# hd-hdr.net
KiCad netlist of a schematic drawn in Altium Designer
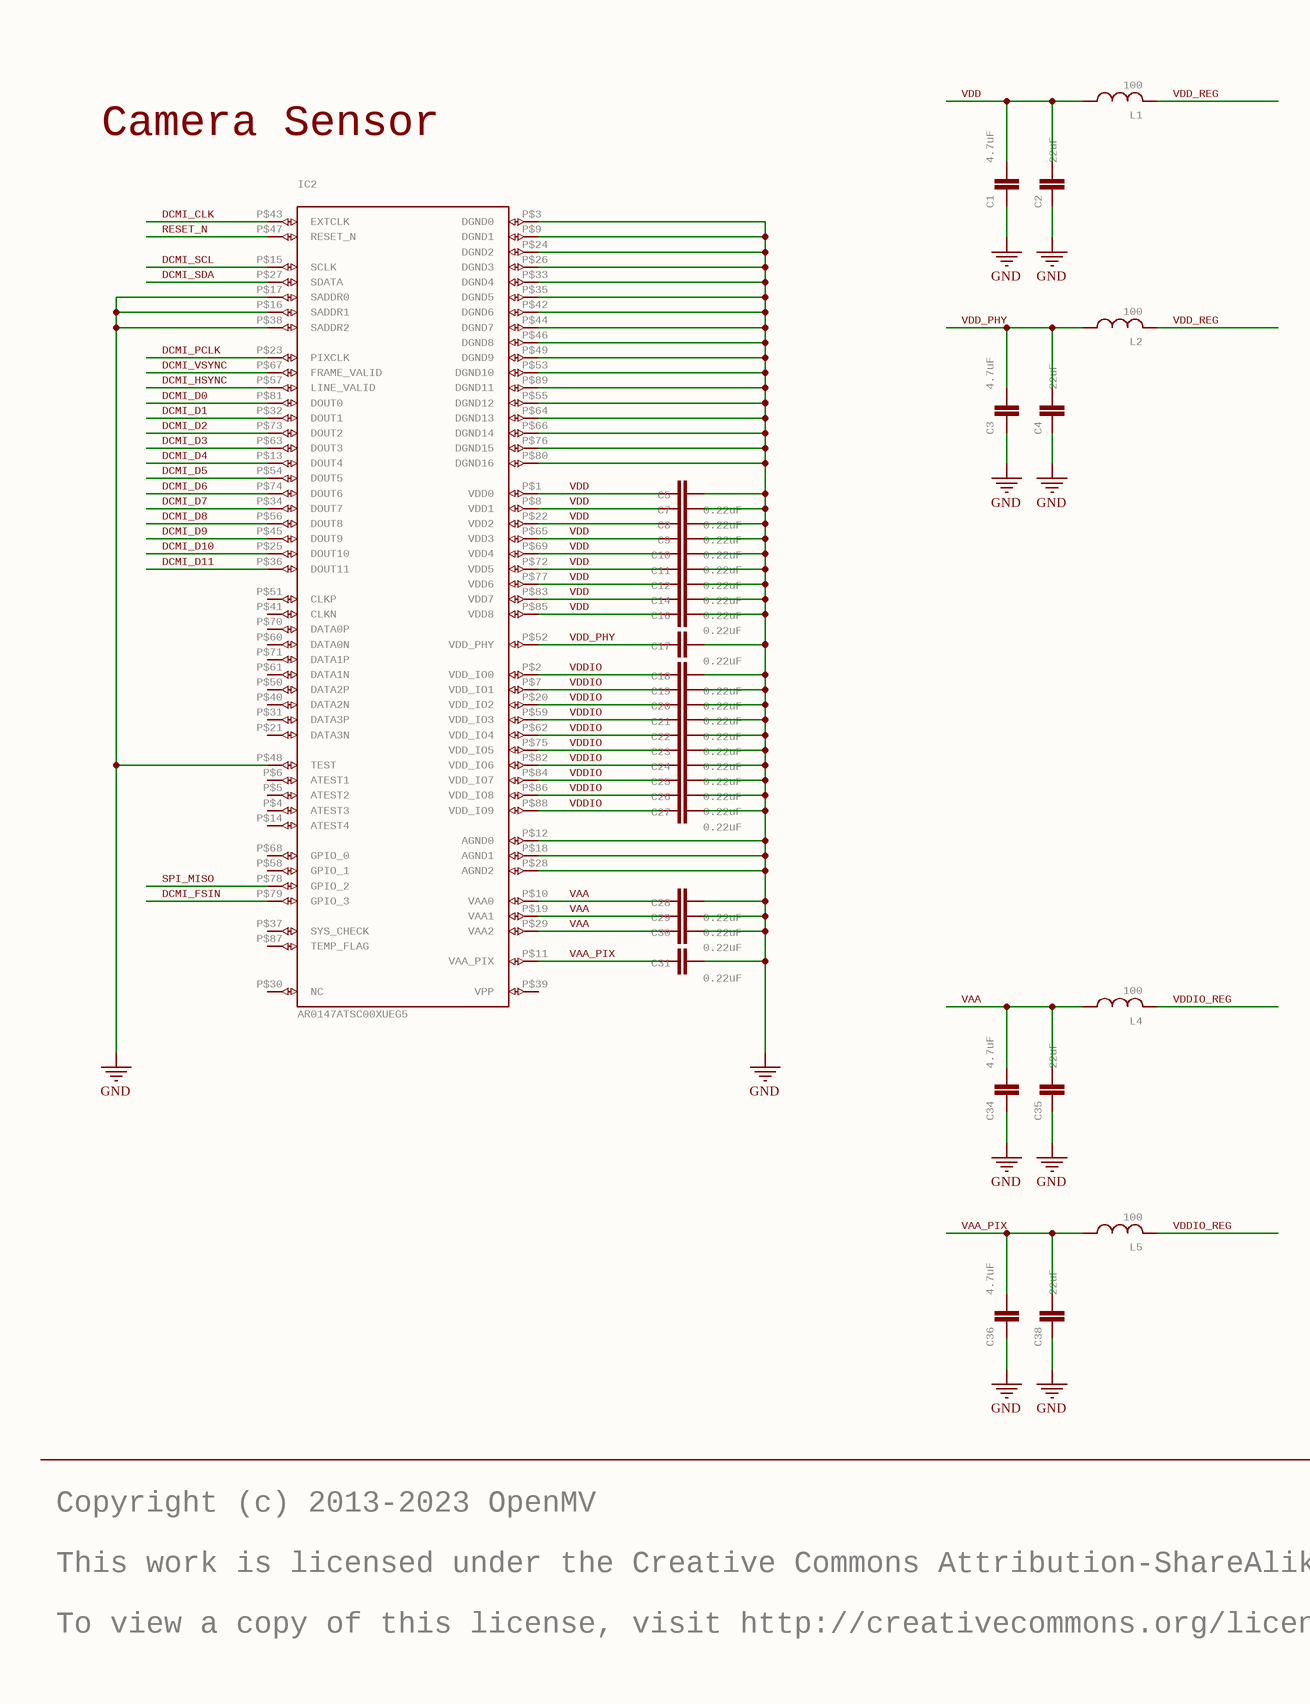
[diagram p0: hd-hdr.SchDoc, left]
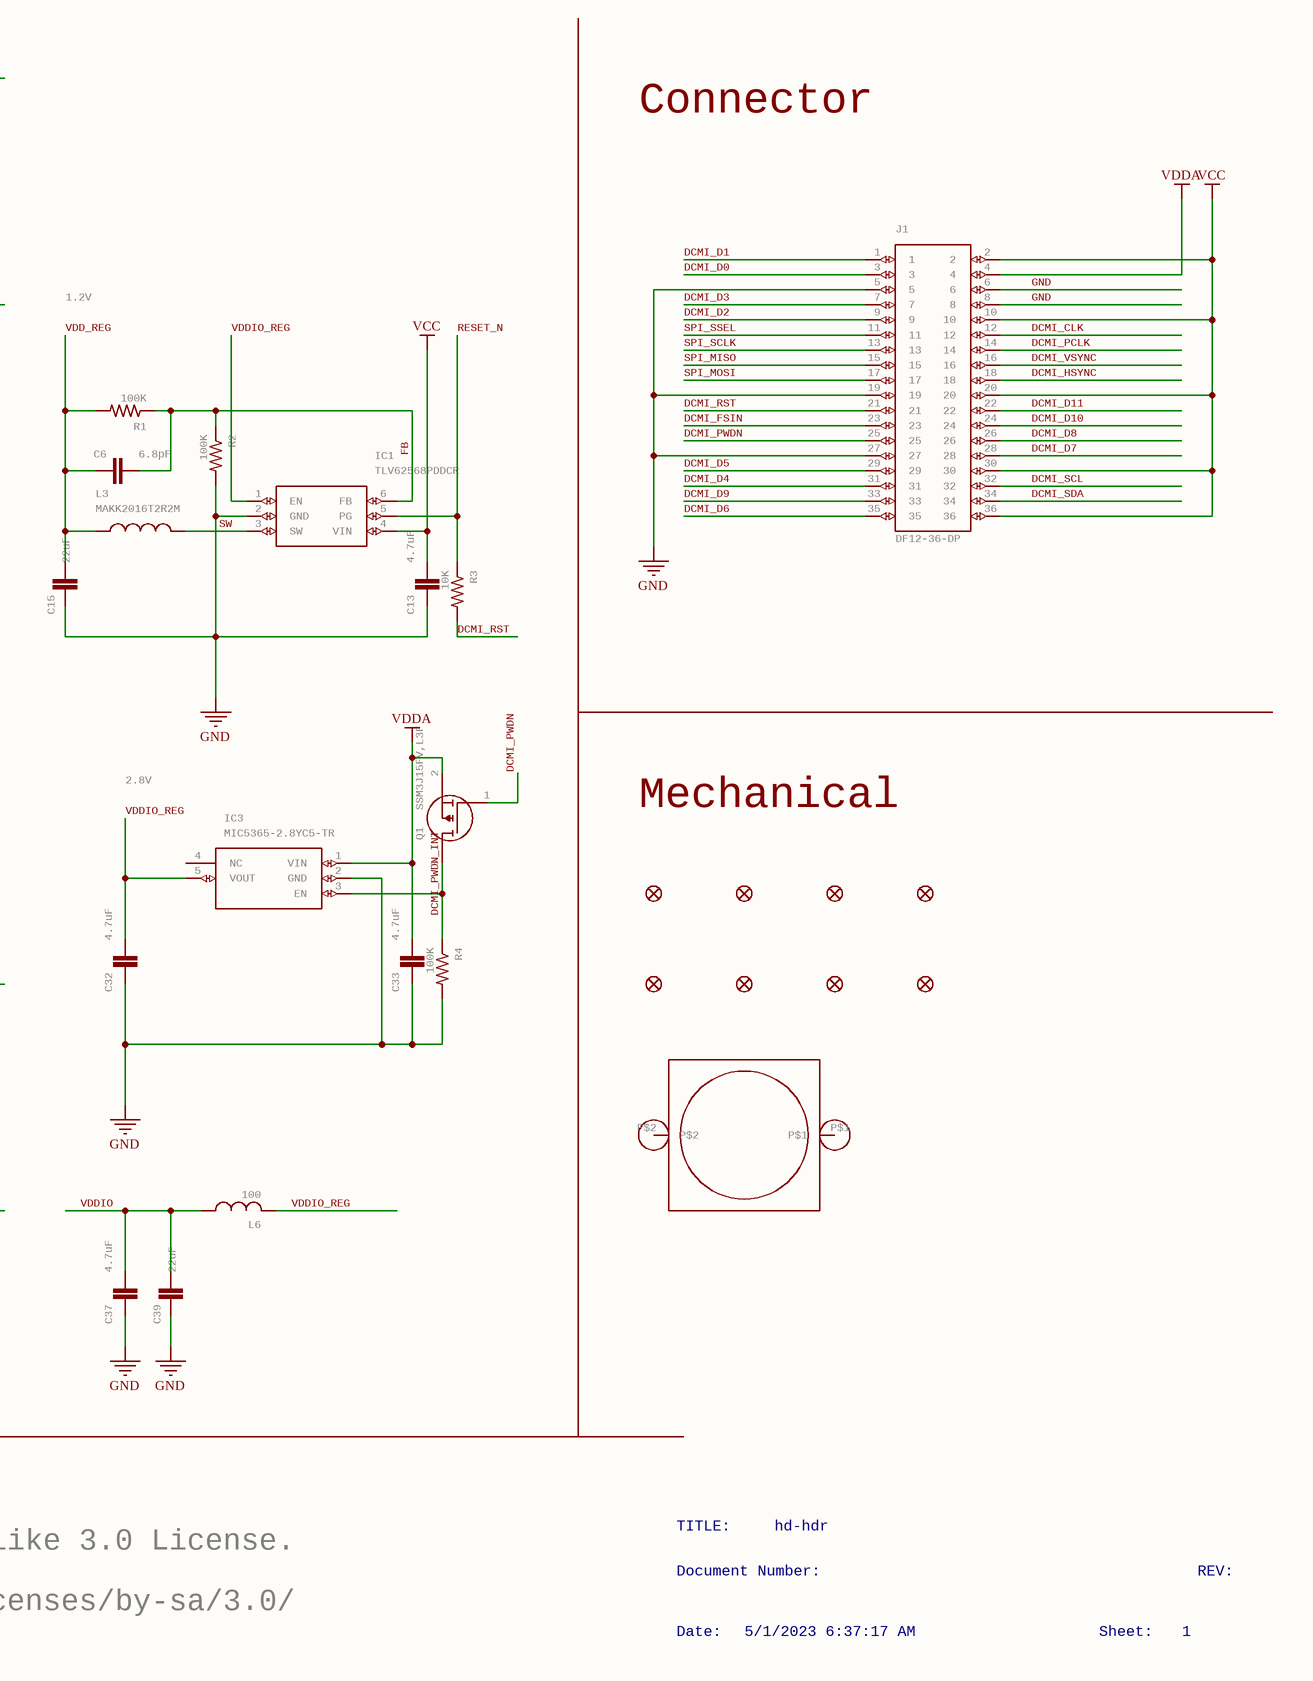
[diagram p1: hd-hdr.SchDoc, right]

(export (version "E")
  (design (tool "Eeschema 10.0.6"))
  (components
    (comp (ref "C1")
      (value "4.7uF")
      (footprint "0402")
      (description "0402 (1005 Metric) Nick Garner - TeleSense")
      (fields (field (name "MPN") "JMK105BBJ475MV-F"))
      (libsource (lib "camera-modules") (part "CAP_0402"))
    )
    (comp (ref "C2")
      (value "22uF")
      (footprint "0805")
      (fields (field (name "MPN") "CL21A226MQQNNNE"))
      (libsource (lib "camera-modules") (part "22UF-0805-6.3V-20%"))
    )
    (comp (ref "C3")
      (value "4.7uF")
      (footprint "0402")
      (description "0402 (1005 Metric) Nick Garner - TeleSense")
      (fields (field (name "MPN") "JMK105BBJ475MV-F"))
      (libsource (lib "camera-modules") (part "CAP_0402"))
    )
    (comp (ref "C4")
      (value "22uF")
      (footprint "0805")
      (fields (field (name "MPN") "CL21A226MQQNNNE"))
      (libsource (lib "camera-modules") (part "22UF-0805-6.3V-20%"))
    )
    (comp (ref "C5")
      (value "0.22uF")
      (footprint "C0201")
      (description "CAPACITOR, European symbol")
      (fields (field (name "MPN") "GRM033R60J224ME15D"))
      (libsource (lib "camera-modules") (part "C-EUC0201"))
    )
    (comp (ref "C6")
      (value "6.8pF")
      (footprint "0402")
      (description "0402 (1005 Metric) Nick Garner - TeleSense")
      (fields (field (name "MPN") "GRM1555C1H6R8DA01D"))
      (libsource (lib "") (part "CAP_0402_1"))
    )
    (comp (ref "C7")
      (value "0.22uF")
      (footprint "C0201")
      (description "CAPACITOR, European symbol")
      (fields (field (name "MPN") "GRM033R60J224ME15D"))
      (libsource (lib "camera-modules") (part "C-EUC0201"))
    )
    (comp (ref "C8")
      (value "0.22uF")
      (footprint "C0201")
      (description "CAPACITOR, European symbol")
      (fields (field (name "MPN") "GRM033R60J224ME15D"))
      (libsource (lib "camera-modules") (part "C-EUC0201"))
    )
    (comp (ref "C9")
      (value "0.22uF")
      (footprint "C0201")
      (description "CAPACITOR, European symbol")
      (fields (field (name "MPN") "GRM033R60J224ME15D"))
      (libsource (lib "camera-modules") (part "C-EUC0201"))
    )
    (comp (ref "C10")
      (value "0.22uF")
      (footprint "C0201")
      (description "CAPACITOR, European symbol")
      (fields (field (name "MPN") "GRM033R60J224ME15D"))
      (libsource (lib "camera-modules") (part "C-EUC0201"))
    )
    (comp (ref "C11")
      (value "0.22uF")
      (footprint "C0201")
      (description "CAPACITOR, European symbol")
      (fields (field (name "MPN") "GRM033R60J224ME15D"))
      (libsource (lib "camera-modules") (part "C-EUC0201"))
    )
    (comp (ref "C12")
      (value "0.22uF")
      (footprint "C0201")
      (description "CAPACITOR, European symbol")
      (fields (field (name "MPN") "GRM033R60J224ME15D"))
      (libsource (lib "camera-modules") (part "C-EUC0201"))
    )
    (comp (ref "C13")
      (value "4.7uF")
      (footprint "0402")
      (description "0402 (1005 Metric) Nick Garner - TeleSense")
      (fields (field (name "MPN") "JMK105BBJ475MV-F"))
      (libsource (lib "camera-modules") (part "CAP_0402"))
    )
    (comp (ref "C14")
      (value "0.22uF")
      (footprint "C0201")
      (description "CAPACITOR, European symbol")
      (fields (field (name "MPN") "GRM033R60J224ME15D"))
      (libsource (lib "camera-modules") (part "C-EUC0201"))
    )
    (comp (ref "C15")
      (value "22uF")
      (footprint "0805")
      (fields (field (name "MPN") "CL21A226MQQNNNE"))
      (libsource (lib "camera-modules") (part "22UF-0805-6.3V-20%"))
    )
    (comp (ref "C16")
      (value "0.22uF")
      (footprint "C0201")
      (description "CAPACITOR, European symbol")
      (fields (field (name "MPN") "GRM033R60J224ME15D"))
      (libsource (lib "camera-modules") (part "C-EUC0201"))
    )
    (comp (ref "C17")
      (value "0.22uF")
      (footprint "C0201")
      (description "CAPACITOR, European symbol")
      (fields (field (name "MPN") "GRM033R60J224ME15D"))
      (libsource (lib "camera-modules") (part "C-EUC0201"))
    )
    (comp (ref "C18")
      (value "0.22uF")
      (footprint "C0201")
      (description "CAPACITOR, European symbol")
      (fields (field (name "MPN") "GRM033R60J224ME15D"))
      (libsource (lib "camera-modules") (part "C-EUC0201"))
    )
    (comp (ref "C19")
      (value "0.22uF")
      (footprint "C0201")
      (description "CAPACITOR, European symbol")
      (fields (field (name "MPN") "GRM033R60J224ME15D"))
      (libsource (lib "camera-modules") (part "C-EUC0201"))
    )
    (comp (ref "C20")
      (value "0.22uF")
      (footprint "C0201")
      (description "CAPACITOR, European symbol")
      (fields (field (name "MPN") "GRM033R60J224ME15D"))
      (libsource (lib "camera-modules") (part "C-EUC0201"))
    )
    (comp (ref "C21")
      (value "0.22uF")
      (footprint "C0201")
      (description "CAPACITOR, European symbol")
      (fields (field (name "MPN") "GRM033R60J224ME15D"))
      (libsource (lib "camera-modules") (part "C-EUC0201"))
    )
    (comp (ref "C22")
      (value "0.22uF")
      (footprint "C0201")
      (description "CAPACITOR, European symbol")
      (fields (field (name "MPN") "GRM033R60J224ME15D"))
      (libsource (lib "camera-modules") (part "C-EUC0201"))
    )
    (comp (ref "C23")
      (value "0.22uF")
      (footprint "C0201")
      (description "CAPACITOR, European symbol")
      (fields (field (name "MPN") "GRM033R60J224ME15D"))
      (libsource (lib "camera-modules") (part "C-EUC0201"))
    )
    (comp (ref "C24")
      (value "0.22uF")
      (footprint "C0201")
      (description "CAPACITOR, European symbol")
      (fields (field (name "MPN") "GRM033R60J224ME15D"))
      (libsource (lib "camera-modules") (part "C-EUC0201"))
    )
    (comp (ref "C25")
      (value "0.22uF")
      (footprint "C0201")
      (description "CAPACITOR, European symbol")
      (fields (field (name "MPN") "GRM033R60J224ME15D"))
      (libsource (lib "camera-modules") (part "C-EUC0201"))
    )
    (comp (ref "C26")
      (value "0.22uF")
      (footprint "C0201")
      (description "CAPACITOR, European symbol")
      (fields (field (name "MPN") "GRM033R60J224ME15D"))
      (libsource (lib "camera-modules") (part "C-EUC0201"))
    )
    (comp (ref "C27")
      (value "0.22uF")
      (footprint "C0201")
      (description "CAPACITOR, European symbol")
      (fields (field (name "MPN") "GRM033R60J224ME15D"))
      (libsource (lib "camera-modules") (part "C-EUC0201"))
    )
    (comp (ref "C28")
      (value "0.22uF")
      (footprint "C0201")
      (description "CAPACITOR, European symbol")
      (fields (field (name "MPN") "GRM033R60J224ME15D"))
      (libsource (lib "camera-modules") (part "C-EUC0201"))
    )
    (comp (ref "C29")
      (value "0.22uF")
      (footprint "C0201")
      (description "CAPACITOR, European symbol")
      (fields (field (name "MPN") "GRM033R60J224ME15D"))
      (libsource (lib "camera-modules") (part "C-EUC0201"))
    )
    (comp (ref "C30")
      (value "0.22uF")
      (footprint "C0201")
      (description "CAPACITOR, European symbol")
      (fields (field (name "MPN") "GRM033R60J224ME15D"))
      (libsource (lib "camera-modules") (part "C-EUC0201"))
    )
    (comp (ref "C31")
      (value "0.22uF")
      (footprint "C0201")
      (description "CAPACITOR, European symbol")
      (fields (field (name "MPN") "GRM033R60J224ME15D"))
      (libsource (lib "camera-modules") (part "C-EUC0201"))
    )
    (comp (ref "C32")
      (value "4.7uF")
      (footprint "0402")
      (description "0402 (1005 Metric) Nick Garner - TeleSense")
      (fields (field (name "MPN") "JMK105BBJ475MV-F"))
      (libsource (lib "camera-modules") (part "CAP_0402"))
    )
    (comp (ref "C33")
      (value "4.7uF")
      (footprint "0402")
      (description "0402 (1005 Metric) Nick Garner - TeleSense")
      (fields (field (name "MPN") "JMK105BBJ475MV-F"))
      (libsource (lib "camera-modules") (part "CAP_0402"))
    )
    (comp (ref "C34")
      (value "4.7uF")
      (footprint "0402")
      (description "0402 (1005 Metric) Nick Garner - TeleSense")
      (fields (field (name "MPN") "JMK105BBJ475MV-F"))
      (libsource (lib "camera-modules") (part "CAP_0402"))
    )
    (comp (ref "C35")
      (value "22uF")
      (footprint "0805")
      (fields (field (name "MPN") "CL21A226MQQNNNE"))
      (libsource (lib "camera-modules") (part "22UF-0805-6.3V-20%"))
    )
    (comp (ref "C36")
      (value "4.7uF")
      (footprint "0402")
      (description "0402 (1005 Metric) Nick Garner - TeleSense")
      (fields (field (name "MPN") "JMK105BBJ475MV-F"))
      (libsource (lib "camera-modules") (part "CAP_0402"))
    )
    (comp (ref "C37")
      (value "4.7uF")
      (footprint "0402")
      (description "0402 (1005 Metric) Nick Garner - TeleSense")
      (fields (field (name "MPN") "JMK105BBJ475MV-F"))
      (libsource (lib "camera-modules") (part "CAP_0402"))
    )
    (comp (ref "C38")
      (value "22uF")
      (footprint "0805")
      (fields (field (name "MPN") "CL21A226MQQNNNE"))
      (libsource (lib "camera-modules") (part "22UF-0805-6.3V-20%"))
    )
    (comp (ref "C39")
      (value "22uF")
      (footprint "0805")
      (fields (field (name "MPN") "CL21A226MQQNNNE"))
      (libsource (lib "camera-modules") (part "22UF-0805-6.3V-20%"))
    )
    (comp (ref "FD1")
      (value "FIDUCIAL1X2")
      (footprint "FIDUCIAL-1X2")
      (fields (field (name "LIBRARYNAME") "SparkFun-Aesthetics"))
      (libsource (lib "camera-modules") (part "FIDUCIAL1X2"))
    )
    (comp (ref "FD2")
      (value "FIDUCIAL1X2")
      (footprint "FIDUCIAL-1X2")
      (fields (field (name "LIBRARYNAME") "SparkFun-Aesthetics"))
      (libsource (lib "camera-modules") (part "FIDUCIAL1X2"))
    )
    (comp (ref "FD3")
      (value "FIDUCIAL1X2")
      (footprint "FIDUCIAL-1X2")
      (fields (field (name "LIBRARYNAME") "SparkFun-Aesthetics"))
      (libsource (lib "camera-modules") (part "FIDUCIAL1X2"))
    )
    (comp (ref "FD4")
      (value "FIDUCIAL1X2")
      (footprint "FIDUCIAL-1X2")
      (fields (field (name "LIBRARYNAME") "SparkFun-Aesthetics"))
      (libsource (lib "camera-modules") (part "FIDUCIAL1X2"))
    )
    (comp (ref "FD5")
      (value "FIDUCIAL1X2")
      (footprint "FIDUCIAL-1X2")
      (fields (field (name "LIBRARYNAME") "SparkFun-Aesthetics"))
      (libsource (lib "camera-modules") (part "FIDUCIAL1X2"))
    )
    (comp (ref "FD6")
      (value "FIDUCIAL1X2")
      (footprint "FIDUCIAL-1X2")
      (fields (field (name "LIBRARYNAME") "SparkFun-Aesthetics"))
      (libsource (lib "camera-modules") (part "FIDUCIAL1X2"))
    )
    (comp (ref "FD7")
      (value "FIDUCIAL1X2")
      (footprint "FIDUCIAL-1X2")
      (fields (field (name "LIBRARYNAME") "SparkFun-Aesthetics"))
      (libsource (lib "camera-modules") (part "FIDUCIAL1X2"))
    )
    (comp (ref "FD8")
      (value "FIDUCIAL1X2")
      (footprint "FIDUCIAL-1X2")
      (fields (field (name "LIBRARYNAME") "SparkFun-Aesthetics"))
      (libsource (lib "camera-modules") (part "FIDUCIAL1X2"))
    )
    (comp (ref "H1")
      (value "LENSMOUNT20MM")
      (footprint "LENSMOUNT-20MM")
      (libsource (lib "camera-modules") (part "LENSMOUNT20MM"))
    )
    (comp (ref "IC1")
      (value "TLV62568PDDCR")
      (footprint "SOT95P280X110-6N")
      (fields (field (name "MOUSER_PART_NUMBER") "595-TLV62568PDDCR"))
      (libsource (lib "camera-modules") (part "TLV62568PDDCR"))
    )
    (comp (ref "IC2")
      (value "AR0147ATSC00XUEG5")
      (footprint "AR0147ATSC00XUEG5")
      (fields (field (name "MPN") "AR0147ATSC00XUEG5-DRBR"))
      (libsource (lib "camera-modules") (part "AR0147ATSC00XUEG5"))
    )
    (comp (ref "IC3")
      (value "MIC5365-2.8YC5-TR")
      (footprint "SOT65P210X110-5N")
      (description "IC REG LINEAR 2.8V 150MA SC70-5   Source:  Datasheet")
      (fields (field (name "MOUSER_PART_NUMBER") "998-MIC5365-2.8YC5TR"))
      (libsource (lib "camera-modules") (part "MIC5365-2.8YC5-TR"))
    )
    (comp (ref "J1")
      (value "DF12-36-DP")
      (footprint "DF12-36-DP")
      (fields (field (name "MPN") "DF12NB(3.0)-36DP-0.5V(51)"))
      (libsource (lib "camera-modules") (part "DF12-36-DP"))
    )
    (comp (ref "L1")
      (value "100")
      (footprint "0402")
      (fields (field (name "MPN") "MFBM1V1005-101-R"))
      (libsource (lib "camera-modules") (part "INDUCTOR_0402"))
    )
    (comp (ref "L2")
      (value "100")
      (footprint "0402")
      (fields (field (name "MPN") "MFBM1V1005-101-R"))
      (libsource (lib "camera-modules") (part "INDUCTOR_0402"))
    )
    (comp (ref "L3")
      (value "MAKK2016T2R2M")
      (footprint "INDC2016X100N")
      (description "INDUCTOR, METAL CORE Check availability")
      (fields (field (name "MF") "Taiyo Yuden"))
      (libsource (lib "camera-modules") (part "MAKK2016T2R2M"))
    )
    (comp (ref "L4")
      (value "100")
      (footprint "0402")
      (fields (field (name "MPN") "MFBM1V1005-101-R"))
      (libsource (lib "camera-modules") (part "INDUCTOR_0402"))
    )
    (comp (ref "L5")
      (value "100")
      (footprint "0402")
      (fields (field (name "MPN") "MFBM1V1005-101-R"))
      (libsource (lib "camera-modules") (part "INDUCTOR_0402"))
    )
    (comp (ref "L6")
      (value "100")
      (footprint "0402")
      (fields (field (name "MPN") "MFBM1V1005-101-R"))
      (libsource (lib "camera-modules") (part "INDUCTOR_0402"))
    )
    (comp (ref "Q1")
      (value "SSM3J15FV,L3F")
      (footprint "SSM3J15FV")
      (description "MOSFET 30 V, P-channel Trench MOSFET   Source:  Datasheet")
      (libsource (lib "camera-modules") (part "PMXB120EPEZ"))
    )
    (comp (ref "R1")
      (value "100K")
      (footprint "R0402")
      (description "RESISTOR, American symbol")
      (fields (field (name "MPN") "AC0402FR-07100KL"))
      (libsource (lib "camera-modules") (part "R-US_R0402"))
    )
    (comp (ref "R2")
      (value "100K")
      (footprint "R0402")
      (description "RESISTOR, American symbol")
      (fields (field (name "MPN") "AC0402FR-07100KL"))
      (libsource (lib "camera-modules") (part "R-US_R0402"))
    )
    (comp (ref "R3")
      (value "10K")
      (footprint "R0402")
      (description "RESISTOR, American symbol")
      (fields (field (name "MPN") "AC0402FR-1310KL"))
      (libsource (lib "camera-modules") (part "R-US_R0402"))
    )
    (comp (ref "R4")
      (value "100K")
      (footprint "R0402")
      (description "RESISTOR, American symbol")
      (fields (field (name "MPN") "AC0402FR-07100KL"))
      (libsource (lib "camera-modules") (part "R-US_R0402"))
    )
  )
  (nets
    (net (code "1") (name "/DCMI_CLK") (class "Default")
      (node (ref "IC2") (pin "P$43") (pinfunction "EXTCLK_P$43") (pintype "bidirectional"))
      (node (ref "J1") (pin "12") (pinfunction "12_12") (pintype "bidirectional"))
    )
    (net (code "2") (name "/DCMI_D0") (class "Default")
      (node (ref "IC2") (pin "P$81") (pinfunction "DOUT0_P$81") (pintype "bidirectional"))
      (node (ref "J1") (pin "3") (pinfunction "3_3") (pintype "bidirectional"))
    )
    (net (code "3") (name "/DCMI_D1") (class "Default")
      (node (ref "IC2") (pin "P$32") (pinfunction "DOUT1_P$32") (pintype "bidirectional"))
      (node (ref "J1") (pin "1") (pinfunction "1_1") (pintype "bidirectional"))
    )
    (net (code "4") (name "/DCMI_D2") (class "Default")
      (node (ref "IC2") (pin "P$73") (pinfunction "DOUT2_P$73") (pintype "bidirectional"))
      (node (ref "J1") (pin "9") (pinfunction "9_9") (pintype "bidirectional"))
    )
    (net (code "5") (name "/DCMI_D3") (class "Default")
      (node (ref "IC2") (pin "P$63") (pinfunction "DOUT3_P$63") (pintype "bidirectional"))
      (node (ref "J1") (pin "7") (pinfunction "7_7") (pintype "bidirectional"))
    )
    (net (code "6") (name "/DCMI_D4") (class "Default")
      (node (ref "IC2") (pin "P$13") (pinfunction "DOUT4_P$13") (pintype "bidirectional"))
      (node (ref "J1") (pin "31") (pinfunction "31_31") (pintype "bidirectional"))
    )
    (net (code "7") (name "/DCMI_D5") (class "Default")
      (node (ref "IC2") (pin "P$54") (pinfunction "DOUT5_P$54") (pintype "bidirectional"))
      (node (ref "J1") (pin "29") (pinfunction "29_29") (pintype "bidirectional"))
    )
    (net (code "8") (name "/DCMI_D6") (class "Default")
      (node (ref "IC2") (pin "P$74") (pinfunction "DOUT6_P$74") (pintype "bidirectional"))
      (node (ref "J1") (pin "35") (pinfunction "35_35") (pintype "bidirectional"))
    )
    (net (code "9") (name "/DCMI_D7") (class "Default")
      (node (ref "IC2") (pin "P$34") (pinfunction "DOUT7_P$34") (pintype "bidirectional"))
      (node (ref "J1") (pin "28") (pinfunction "28_28") (pintype "bidirectional"))
    )
    (net (code "10") (name "/DCMI_D8") (class "Default")
      (node (ref "IC2") (pin "P$56") (pinfunction "DOUT8_P$56") (pintype "bidirectional"))
      (node (ref "J1") (pin "26") (pinfunction "26_26") (pintype "bidirectional"))
    )
    (net (code "11") (name "/DCMI_D9") (class "Default")
      (node (ref "IC2") (pin "P$45") (pinfunction "DOUT9_P$45") (pintype "bidirectional"))
      (node (ref "J1") (pin "33") (pinfunction "33_33") (pintype "bidirectional"))
    )
    (net (code "12") (name "/DCMI_D10") (class "Default")
      (node (ref "IC2") (pin "P$25") (pinfunction "DOUT10_P$25") (pintype "bidirectional"))
      (node (ref "J1") (pin "24") (pinfunction "24_24") (pintype "bidirectional"))
    )
    (net (code "13") (name "/DCMI_D11") (class "Default")
      (node (ref "IC2") (pin "P$36") (pinfunction "DOUT11_P$36") (pintype "bidirectional"))
      (node (ref "J1") (pin "22") (pinfunction "22_22") (pintype "bidirectional"))
    )
    (net (code "14") (name "/DCMI_FSIN") (class "Default")
      (node (ref "IC2") (pin "P$79") (pinfunction "GPIO_3_P$79") (pintype "bidirectional"))
      (node (ref "J1") (pin "23") (pinfunction "23_23") (pintype "bidirectional"))
    )
    (net (code "15") (name "/DCMI_HSYNC") (class "Default")
      (node (ref "IC2") (pin "P$57") (pinfunction "LINE_VALID_P$57") (pintype "bidirectional"))
      (node (ref "J1") (pin "18") (pinfunction "18_18") (pintype "bidirectional"))
    )
    (net (code "16") (name "/DCMI_PCLK") (class "Default")
      (node (ref "IC2") (pin "P$23") (pinfunction "PIXCLK_P$23") (pintype "bidirectional"))
      (node (ref "J1") (pin "14") (pinfunction "14_14") (pintype "bidirectional"))
    )
    (net (code "17") (name "/DCMI_PWDN") (class "Default")
      (node (ref "J1") (pin "25") (pinfunction "25_25") (pintype "bidirectional"))
      (node (ref "Q1") (pin "1") (pinfunction "G_1") (pintype "bidirectional"))
    )
    (net (code "18") (name "/DCMI_PWDN_INT") (class "Default")
      (node (ref "IC3") (pin "3") (pinfunction "EN_3") (pintype "bidirectional"))
      (node (ref "Q1") (pin "3") (pinfunction "D_3") (pintype "bidirectional"))
      (node (ref "R4") (pin "1") (pinfunction "1_1") (pintype "passive"))
    )
    (net (code "19") (name "/DCMI_RST") (class "Default")
      (node (ref "J1") (pin "21") (pinfunction "21_21") (pintype "bidirectional"))
      (node (ref "R3") (pin "2") (pinfunction "2_2") (pintype "passive"))
    )
    (net (code "20") (name "/DCMI_SCL") (class "Default")
      (node (ref "IC2") (pin "P$15") (pinfunction "SCLK_P$15") (pintype "bidirectional"))
      (node (ref "J1") (pin "32") (pinfunction "32_32") (pintype "bidirectional"))
    )
    (net (code "21") (name "/DCMI_SDA") (class "Default")
      (node (ref "IC2") (pin "P$27") (pinfunction "SDATA_P$27") (pintype "bidirectional"))
      (node (ref "J1") (pin "34") (pinfunction "34_34") (pintype "bidirectional"))
    )
    (net (code "22") (name "/DCMI_VSYNC") (class "Default")
      (node (ref "IC2") (pin "P$67") (pinfunction "FRAME_VALID_P$67") (pintype "bidirectional"))
      (node (ref "J1") (pin "16") (pinfunction "16_16") (pintype "bidirectional"))
    )
    (net (code "23") (name "/FB") (class "Default")
      (node (ref "C6") (pin "2") (pinfunction "2_2") (pintype "passive"))
      (node (ref "IC1") (pin "6") (pinfunction "FB_6") (pintype "bidirectional"))
      (node (ref "R1") (pin "1") (pinfunction "1_1") (pintype "passive"))
      (node (ref "R2") (pin "1") (pinfunction "1_1") (pintype "passive"))
    )
    (net (code "24") (name "/RESET_N") (class "Default")
      (node (ref "IC1") (pin "5") (pinfunction "PG_5") (pintype "bidirectional"))
      (node (ref "IC2") (pin "P$47") (pinfunction "RESET_N_P$47") (pintype "bidirectional"))
      (node (ref "R3") (pin "1") (pinfunction "1_1") (pintype "passive"))
    )
    (net (code "25") (name "/SPI_MISO") (class "Default")
      (node (ref "IC2") (pin "P$78") (pinfunction "GPIO_2_P$78") (pintype "bidirectional"))
      (node (ref "J1") (pin "15") (pinfunction "15_15") (pintype "bidirectional"))
    )
    (net (code "26") (name "/SPI_MOSI") (class "Default")
      (node (ref "J1") (pin "17") (pinfunction "17_17") (pintype "bidirectional"))
    )
    (net (code "27") (name "/SPI_SCLK") (class "Default")
      (node (ref "J1") (pin "13") (pinfunction "13_13") (pintype "bidirectional"))
    )
    (net (code "28") (name "/SPI_SSEL") (class "Default")
      (node (ref "J1") (pin "11") (pinfunction "11_11") (pintype "bidirectional"))
    )
    (net (code "29") (name "/SW") (class "Default")
      (node (ref "IC1") (pin "3") (pinfunction "SW_3") (pintype "bidirectional"))
      (node (ref "L3") (pin "2") (pinfunction "2_2") (pintype "passive"))
    )
    (net (code "30") (name "/VAA") (class "Default")
      (node (ref "C28") (pin "1") (pinfunction "1_1") (pintype "passive"))
      (node (ref "C29") (pin "1") (pinfunction "1_1") (pintype "passive"))
      (node (ref "C30") (pin "1") (pinfunction "1_1") (pintype "passive"))
      (node (ref "C34") (pin "2") (pinfunction "2_2") (pintype "passive"))
      (node (ref "C35") (pin "2") (pinfunction "2_2") (pintype "passive"))
      (node (ref "IC2") (pin "P$10") (pinfunction "VAA0_P$10") (pintype "bidirectional"))
      (node (ref "IC2") (pin "P$19") (pinfunction "VAA1_P$19") (pintype "bidirectional"))
      (node (ref "IC2") (pin "P$29") (pinfunction "VAA2_P$29") (pintype "bidirectional"))
      (node (ref "L4") (pin "1") (pinfunction "P$1_1") (pintype "passive"))
    )
    (net (code "31") (name "/VAA_PIX") (class "Default")
      (node (ref "C31") (pin "1") (pinfunction "1_1") (pintype "passive"))
      (node (ref "C36") (pin "2") (pinfunction "2_2") (pintype "passive"))
      (node (ref "C38") (pin "2") (pinfunction "2_2") (pintype "passive"))
      (node (ref "IC2") (pin "P$11") (pinfunction "VAA_PIX_P$11") (pintype "bidirectional"))
      (node (ref "L5") (pin "1") (pinfunction "P$1_1") (pintype "passive"))
    )
    (net (code "32") (name "/VDD") (class "Default")
      (node (ref "C1") (pin "2") (pinfunction "2_2") (pintype "passive"))
      (node (ref "C10") (pin "1") (pinfunction "1_1") (pintype "passive"))
      (node (ref "C11") (pin "1") (pinfunction "1_1") (pintype "passive"))
      (node (ref "C12") (pin "1") (pinfunction "1_1") (pintype "passive"))
      (node (ref "C14") (pin "1") (pinfunction "1_1") (pintype "passive"))
      (node (ref "C16") (pin "1") (pinfunction "1_1") (pintype "passive"))
      (node (ref "C2") (pin "2") (pinfunction "2_2") (pintype "passive"))
      (node (ref "C5") (pin "1") (pinfunction "1_1") (pintype "passive"))
      (node (ref "C7") (pin "1") (pinfunction "1_1") (pintype "passive"))
      (node (ref "C8") (pin "1") (pinfunction "1_1") (pintype "passive"))
      (node (ref "C9") (pin "1") (pinfunction "1_1") (pintype "passive"))
      (node (ref "IC2") (pin "P$1") (pinfunction "VDD0_P$1") (pintype "bidirectional"))
      (node (ref "IC2") (pin "P$22") (pinfunction "VDD2_P$22") (pintype "bidirectional"))
      (node (ref "IC2") (pin "P$65") (pinfunction "VDD3_P$65") (pintype "bidirectional"))
      (node (ref "IC2") (pin "P$69") (pinfunction "VDD4_P$69") (pintype "bidirectional"))
      (node (ref "IC2") (pin "P$72") (pinfunction "VDD5_P$72") (pintype "bidirectional"))
      (node (ref "IC2") (pin "P$77") (pinfunction "VDD6_P$77") (pintype "bidirectional"))
      (node (ref "IC2") (pin "P$8") (pinfunction "VDD1_P$8") (pintype "bidirectional"))
      (node (ref "IC2") (pin "P$83") (pinfunction "VDD7_P$83") (pintype "bidirectional"))
      (node (ref "IC2") (pin "P$85") (pinfunction "VDD8_P$85") (pintype "bidirectional"))
      (node (ref "L1") (pin "1") (pinfunction "P$1_1") (pintype "passive"))
    )
    (net (code "33") (name "/VDDIO") (class "Default")
      (node (ref "C18") (pin "1") (pinfunction "1_1") (pintype "passive"))
      (node (ref "C19") (pin "1") (pinfunction "1_1") (pintype "passive"))
      (node (ref "C20") (pin "1") (pinfunction "1_1") (pintype "passive"))
      (node (ref "C21") (pin "1") (pinfunction "1_1") (pintype "passive"))
      (node (ref "C22") (pin "1") (pinfunction "1_1") (pintype "passive"))
      (node (ref "C23") (pin "1") (pinfunction "1_1") (pintype "passive"))
      (node (ref "C24") (pin "1") (pinfunction "1_1") (pintype "passive"))
      (node (ref "C25") (pin "1") (pinfunction "1_1") (pintype "passive"))
      (node (ref "C26") (pin "1") (pinfunction "1_1") (pintype "passive"))
      (node (ref "C27") (pin "1") (pinfunction "1_1") (pintype "passive"))
      (node (ref "C37") (pin "2") (pinfunction "2_2") (pintype "passive"))
      (node (ref "C39") (pin "2") (pinfunction "2_2") (pintype "passive"))
      (node (ref "IC2") (pin "P$2") (pinfunction "VDD_IO0_P$2") (pintype "bidirectional"))
      (node (ref "IC2") (pin "P$20") (pinfunction "VDD_IO2_P$20") (pintype "bidirectional"))
      (node (ref "IC2") (pin "P$59") (pinfunction "VDD_IO3_P$59") (pintype "bidirectional"))
      (node (ref "IC2") (pin "P$62") (pinfunction "VDD_IO4_P$62") (pintype "bidirectional"))
      (node (ref "IC2") (pin "P$7") (pinfunction "VDD_IO1_P$7") (pintype "bidirectional"))
      (node (ref "IC2") (pin "P$75") (pinfunction "VDD_IO5_P$75") (pintype "bidirectional"))
      (node (ref "IC2") (pin "P$82") (pinfunction "VDD_IO6_P$82") (pintype "bidirectional"))
      (node (ref "IC2") (pin "P$84") (pinfunction "VDD_IO7_P$84") (pintype "bidirectional"))
      (node (ref "IC2") (pin "P$86") (pinfunction "VDD_IO8_P$86") (pintype "bidirectional"))
      (node (ref "IC2") (pin "P$88") (pinfunction "VDD_IO9_P$88") (pintype "bidirectional"))
      (node (ref "L6") (pin "1") (pinfunction "P$1_1") (pintype "passive"))
    )
    (net (code "34") (name "/VDDIO_REG") (class "Default")
      (node (ref "C32") (pin "2") (pinfunction "2_2") (pintype "passive"))
      (node (ref "IC1") (pin "1") (pinfunction "EN_1") (pintype "bidirectional"))
      (node (ref "IC3") (pin "5") (pinfunction "VOUT_5") (pintype "bidirectional"))
      (node (ref "L4") (pin "2") (pinfunction "P$2_2") (pintype "passive"))
      (node (ref "L5") (pin "2") (pinfunction "P$2_2") (pintype "passive"))
      (node (ref "L6") (pin "2") (pinfunction "P$2_2") (pintype "passive"))
    )
    (net (code "35") (name "/VDD_PHY") (class "Default")
      (node (ref "C17") (pin "1") (pinfunction "1_1") (pintype "passive"))
      (node (ref "C3") (pin "2") (pinfunction "2_2") (pintype "passive"))
      (node (ref "C4") (pin "2") (pinfunction "2_2") (pintype "passive"))
      (node (ref "IC2") (pin "P$52") (pinfunction "VDD_PHY_P$52") (pintype "bidirectional"))
      (node (ref "L2") (pin "1") (pinfunction "P$1_1") (pintype "passive"))
    )
    (net (code "36") (name "/VDD_REG") (class "Default")
      (node (ref "C15") (pin "2") (pinfunction "2_2") (pintype "passive"))
      (node (ref "C6") (pin "1") (pinfunction "1_1") (pintype "passive"))
      (node (ref "L1") (pin "2") (pinfunction "P$2_2") (pintype "passive"))
      (node (ref "L2") (pin "2") (pinfunction "P$2_2") (pintype "passive"))
      (node (ref "L3") (pin "1") (pinfunction "1_1") (pintype "passive"))
      (node (ref "R1") (pin "2") (pinfunction "2_2") (pintype "passive"))
    )
    (net (code "37") (name "GND") (class "Default")
      (node (ref "C1") (pin "1") (pinfunction "1_1") (pintype "passive"))
      (node (ref "C10") (pin "2") (pinfunction "2_2") (pintype "passive"))
      (node (ref "C11") (pin "2") (pinfunction "2_2") (pintype "passive"))
      (node (ref "C12") (pin "2") (pinfunction "2_2") (pintype "passive"))
      (node (ref "C13") (pin "1") (pinfunction "1_1") (pintype "passive"))
      (node (ref "C14") (pin "2") (pinfunction "2_2") (pintype "passive"))
      (node (ref "C15") (pin "1") (pinfunction "1_1") (pintype "passive"))
      (node (ref "C16") (pin "2") (pinfunction "2_2") (pintype "passive"))
      (node (ref "C17") (pin "2") (pinfunction "2_2") (pintype "passive"))
      (node (ref "C18") (pin "2") (pinfunction "2_2") (pintype "passive"))
      (node (ref "C19") (pin "2") (pinfunction "2_2") (pintype "passive"))
      (node (ref "C2") (pin "1") (pinfunction "1_1") (pintype "passive"))
      (node (ref "C20") (pin "2") (pinfunction "2_2") (pintype "passive"))
      (node (ref "C21") (pin "2") (pinfunction "2_2") (pintype "passive"))
      (node (ref "C22") (pin "2") (pinfunction "2_2") (pintype "passive"))
      (node (ref "C23") (pin "2") (pinfunction "2_2") (pintype "passive"))
      (node (ref "C24") (pin "2") (pinfunction "2_2") (pintype "passive"))
      (node (ref "C25") (pin "2") (pinfunction "2_2") (pintype "passive"))
      (node (ref "C26") (pin "2") (pinfunction "2_2") (pintype "passive"))
      (node (ref "C27") (pin "2") (pinfunction "2_2") (pintype "passive"))
      (node (ref "C28") (pin "2") (pinfunction "2_2") (pintype "passive"))
      (node (ref "C29") (pin "2") (pinfunction "2_2") (pintype "passive"))
      (node (ref "C3") (pin "1") (pinfunction "1_1") (pintype "passive"))
      (node (ref "C30") (pin "2") (pinfunction "2_2") (pintype "passive"))
      (node (ref "C31") (pin "2") (pinfunction "2_2") (pintype "passive"))
      (node (ref "C32") (pin "1") (pinfunction "1_1") (pintype "passive"))
      (node (ref "C33") (pin "1") (pinfunction "1_1") (pintype "passive"))
      (node (ref "C34") (pin "1") (pinfunction "1_1") (pintype "passive"))
      (node (ref "C35") (pin "1") (pinfunction "1_1") (pintype "passive"))
      (node (ref "C36") (pin "1") (pinfunction "1_1") (pintype "passive"))
      (node (ref "C37") (pin "1") (pinfunction "1_1") (pintype "passive"))
      (node (ref "C38") (pin "1") (pinfunction "1_1") (pintype "passive"))
      (node (ref "C39") (pin "1") (pinfunction "1_1") (pintype "passive"))
      (node (ref "C4") (pin "1") (pinfunction "1_1") (pintype "passive"))
      (node (ref "C5") (pin "2") (pinfunction "2_2") (pintype "passive"))
      (node (ref "C7") (pin "2") (pinfunction "2_2") (pintype "passive"))
      (node (ref "C8") (pin "2") (pinfunction "2_2") (pintype "passive"))
      (node (ref "C9") (pin "2") (pinfunction "2_2") (pintype "passive"))
      (node (ref "IC1") (pin "2") (pinfunction "GND_2") (pintype "bidirectional"))
      (node (ref "IC2") (pin "P$12") (pinfunction "AGND0_P$12") (pintype "bidirectional"))
      (node (ref "IC2") (pin "P$16") (pinfunction "SADDR1_P$16") (pintype "bidirectional"))
      (node (ref "IC2") (pin "P$17") (pinfunction "SADDR0_P$17") (pintype "bidirectional"))
      (node (ref "IC2") (pin "P$18") (pinfunction "AGND1_P$18") (pintype "bidirectional"))
      (node (ref "IC2") (pin "P$24") (pinfunction "DGND2_P$24") (pintype "bidirectional"))
      (node (ref "IC2") (pin "P$26") (pinfunction "DGND3_P$26") (pintype "bidirectional"))
      (node (ref "IC2") (pin "P$28") (pinfunction "AGND2_P$28") (pintype "bidirectional"))
      (node (ref "IC2") (pin "P$3") (pinfunction "DGND0_P$3") (pintype "bidirectional"))
      (node (ref "IC2") (pin "P$33") (pinfunction "DGND4_P$33") (pintype "bidirectional"))
      (node (ref "IC2") (pin "P$35") (pinfunction "DGND5_P$35") (pintype "bidirectional"))
      (node (ref "IC2") (pin "P$38") (pinfunction "SADDR2_P$38") (pintype "bidirectional"))
      (node (ref "IC2") (pin "P$42") (pinfunction "DGND6_P$42") (pintype "bidirectional"))
      (node (ref "IC2") (pin "P$44") (pinfunction "DGND7_P$44") (pintype "bidirectional"))
      (node (ref "IC2") (pin "P$46") (pinfunction "DGND8_P$46") (pintype "bidirectional"))
      (node (ref "IC2") (pin "P$48") (pinfunction "TEST_P$48") (pintype "bidirectional"))
      (node (ref "IC2") (pin "P$49") (pinfunction "DGND9_P$49") (pintype "bidirectional"))
      (node (ref "IC2") (pin "P$53") (pinfunction "DGND10_P$53") (pintype "bidirectional"))
      (node (ref "IC2") (pin "P$55") (pinfunction "DGND12_P$55") (pintype "bidirectional"))
      (node (ref "IC2") (pin "P$64") (pinfunction "DGND13_P$64") (pintype "bidirectional"))
      (node (ref "IC2") (pin "P$66") (pinfunction "DGND14_P$66") (pintype "bidirectional"))
      (node (ref "IC2") (pin "P$76") (pinfunction "DGND15_P$76") (pintype "bidirectional"))
      (node (ref "IC2") (pin "P$80") (pinfunction "DGND16_P$80") (pintype "bidirectional"))
      (node (ref "IC2") (pin "P$89") (pinfunction "DGND11_P$89") (pintype "bidirectional"))
      (node (ref "IC2") (pin "P$9") (pinfunction "DGND1_P$9") (pintype "bidirectional"))
      (node (ref "IC3") (pin "2") (pinfunction "GND_2") (pintype "bidirectional"))
      (node (ref "J1") (pin "19") (pinfunction "19_19") (pintype "bidirectional"))
      (node (ref "J1") (pin "27") (pinfunction "27_27") (pintype "bidirectional"))
      (node (ref "J1") (pin "5") (pinfunction "5_5") (pintype "bidirectional"))
      (node (ref "J1") (pin "6") (pinfunction "6_6") (pintype "bidirectional"))
      (node (ref "J1") (pin "8") (pinfunction "8_8") (pintype "bidirectional"))
      (node (ref "R2") (pin "2") (pinfunction "2_2") (pintype "passive"))
      (node (ref "R4") (pin "2") (pinfunction "2_2") (pintype "passive"))
    )
    (net (code "38") (name "VCC") (class "Default")
      (node (ref "C13") (pin "2") (pinfunction "2_2") (pintype "passive"))
      (node (ref "IC1") (pin "4") (pinfunction "VIN_4") (pintype "bidirectional"))
      (node (ref "J1") (pin "10") (pinfunction "10_10") (pintype "bidirectional"))
      (node (ref "J1") (pin "2") (pinfunction "2_2") (pintype "bidirectional"))
      (node (ref "J1") (pin "20") (pinfunction "20_20") (pintype "bidirectional"))
      (node (ref "J1") (pin "30") (pinfunction "30_30") (pintype "bidirectional"))
      (node (ref "J1") (pin "36") (pinfunction "36_36") (pintype "bidirectional"))
    )
    (net (code "39") (name "VDDA") (class "Default")
      (node (ref "C33") (pin "2") (pinfunction "2_2") (pintype "passive"))
      (node (ref "IC3") (pin "1") (pinfunction "VIN_1") (pintype "bidirectional"))
      (node (ref "J1") (pin "4") (pinfunction "4_4") (pintype "bidirectional"))
      (node (ref "Q1") (pin "2") (pinfunction "S_2") (pintype "bidirectional"))
    )
    (net (code "40") (name "unconnected-(H1-PadP$1)") (class "Default")
      (node (ref "H1") (pin "P$1") (pinfunction "P$1_P$1") (pintype "power_in"))
    )
    (net (code "41") (name "unconnected-(H1-PadP$2)") (class "Default")
      (node (ref "H1") (pin "P$2") (pinfunction "P$2_P$2") (pintype "power_in"))
    )
    (net (code "42") (name "unconnected-(IC2-ATEST1-PadP$6)") (class "Default")
      (node (ref "IC2") (pin "P$6") (pinfunction "ATEST1_P$6") (pintype "bidirectional"))
    )
    (net (code "43") (name "unconnected-(IC2-ATEST2-PadP$5)") (class "Default")
      (node (ref "IC2") (pin "P$5") (pinfunction "ATEST2_P$5") (pintype "bidirectional"))
    )
    (net (code "44") (name "unconnected-(IC2-ATEST3-PadP$4)") (class "Default")
      (node (ref "IC2") (pin "P$4") (pinfunction "ATEST3_P$4") (pintype "bidirectional"))
    )
    (net (code "45") (name "unconnected-(IC2-ATEST4-PadP$14)") (class "Default")
      (node (ref "IC2") (pin "P$14") (pinfunction "ATEST4_P$14") (pintype "bidirectional"))
    )
    (net (code "46") (name "unconnected-(IC2-CLKN-PadP$41)") (class "Default")
      (node (ref "IC2") (pin "P$41") (pinfunction "CLKN_P$41") (pintype "bidirectional"))
    )
    (net (code "47") (name "unconnected-(IC2-CLKP-PadP$51)") (class "Default")
      (node (ref "IC2") (pin "P$51") (pinfunction "CLKP_P$51") (pintype "bidirectional"))
    )
    (net (code "48") (name "unconnected-(IC2-DATA0N-PadP$60)") (class "Default")
      (node (ref "IC2") (pin "P$60") (pinfunction "DATA0N_P$60") (pintype "bidirectional"))
    )
    (net (code "49") (name "unconnected-(IC2-DATA0P-PadP$70)") (class "Default")
      (node (ref "IC2") (pin "P$70") (pinfunction "DATA0P_P$70") (pintype "bidirectional"))
    )
    (net (code "50") (name "unconnected-(IC2-DATA1N-PadP$61)") (class "Default")
      (node (ref "IC2") (pin "P$61") (pinfunction "DATA1N_P$61") (pintype "bidirectional"))
    )
    (net (code "51") (name "unconnected-(IC2-DATA1P-PadP$71)") (class "Default")
      (node (ref "IC2") (pin "P$71") (pinfunction "DATA1P_P$71") (pintype "bidirectional"))
    )
    (net (code "52") (name "unconnected-(IC2-DATA2N-PadP$40)") (class "Default")
      (node (ref "IC2") (pin "P$40") (pinfunction "DATA2N_P$40") (pintype "bidirectional"))
    )
    (net (code "53") (name "unconnected-(IC2-DATA2P-PadP$50)") (class "Default")
      (node (ref "IC2") (pin "P$50") (pinfunction "DATA2P_P$50") (pintype "bidirectional"))
    )
    (net (code "54") (name "unconnected-(IC2-DATA3N-PadP$21)") (class "Default")
      (node (ref "IC2") (pin "P$21") (pinfunction "DATA3N_P$21") (pintype "bidirectional"))
    )
    (net (code "55") (name "unconnected-(IC2-DATA3P-PadP$31)") (class "Default")
      (node (ref "IC2") (pin "P$31") (pinfunction "DATA3P_P$31") (pintype "bidirectional"))
    )
    (net (code "56") (name "unconnected-(IC2-GPIO_0-PadP$68)") (class "Default")
      (node (ref "IC2") (pin "P$68") (pinfunction "GPIO_0_P$68") (pintype "bidirectional"))
    )
    (net (code "57") (name "unconnected-(IC2-GPIO_1-PadP$58)") (class "Default")
      (node (ref "IC2") (pin "P$58") (pinfunction "GPIO_1_P$58") (pintype "bidirectional"))
    )
    (net (code "58") (name "unconnected-(IC2-NC-PadP$30)") (class "Default")
      (node (ref "IC2") (pin "P$30") (pinfunction "NC_P$30") (pintype "bidirectional"))
    )
    (net (code "59") (name "unconnected-(IC2-SYS_CHECK-PadP$37)") (class "Default")
      (node (ref "IC2") (pin "P$37") (pinfunction "SYS_CHECK_P$37") (pintype "bidirectional"))
    )
    (net (code "60") (name "unconnected-(IC2-TEMP_FLAG-PadP$87)") (class "Default")
      (node (ref "IC2") (pin "P$87") (pinfunction "TEMP_FLAG_P$87") (pintype "bidirectional"))
    )
    (net (code "61") (name "unconnected-(IC2-VPP-PadP$39)") (class "Default")
      (node (ref "IC2") (pin "P$39") (pinfunction "VPP_P$39") (pintype "bidirectional"))
    )
    (net (code "62") (name "unconnected-(IC3-NC-Pad4)") (class "Default")
      (node (ref "IC3") (pin "4") (pinfunction "NC_4") (pintype "passive"))
    )
  )
)
